# External_ADC.net
KiCad netlist of a schematic drawn in Altium Designer
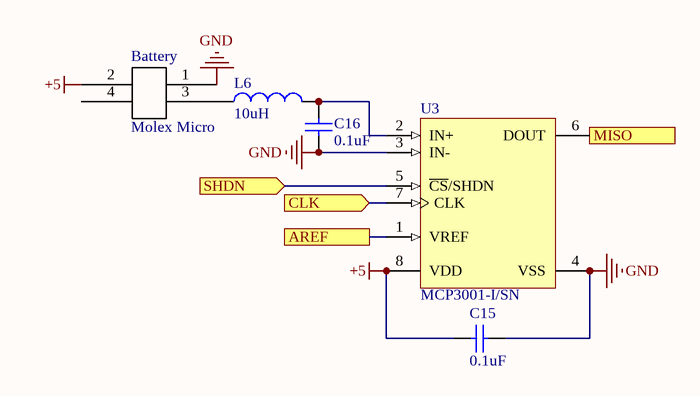
[diagram p0: External ADC.SchDoc]

(export (version "E")
  (design (tool "Eeschema 10.0.6"))
  (components
    (comp (ref "Battery")
      (value "Molex Micro")
      (footprint "0430450427")
      (description "Molex micro-fit 3.0, P/N 0430450427")
      (libsource (lib "Husky Robotics Standard Library 2019-2020") (part "Molex micro-fit 4-pin (dual row schematic)"))
    )
    (comp (ref "C15")
      (value "0.1uF")
      (footprint "CAPC2013X94X50LL20T25")
      (description "Chip Capacitor, 0.1 uF, +/- 5%, 50 V, -55 to 125 degC, 0805 (2012 Metric), RoHS, Tape and Reel")
      (fields (field (name "TOLERANCE") "5%") (field (name "MANUFACTURER") "AVX"))
      (libsource (lib "Altium Content Vault") (part "CAP-NP-2"))
    )
    (comp (ref "C16")
      (value "0.1uF")
      (footprint "CAPC2013X94X50LL20T25")
      (description "Chip Capacitor, 0.1 uF, +/- 5%, 50 V, -55 to 125 degC, 0805 (2012 Metric), RoHS, Tape and Reel")
      (fields (field (name "TOLERANCE") "5%") (field (name "MANUFACTURER") "AVX"))
      (libsource (lib "Altium Content Vault") (part "CAP-NP-2"))
    )
    (comp (ref "L6")
      (value "10uH")
      (footprint "TDK-IND0805-125_V")
      (description "Multilayer Inductor, 10 uH, ±20%, 300 mOhm, 50MHz, 0805(2012)")
      (fields (field (name "PARTNUMBER") "MLZ2012N100LT"))
      (libsource (lib "Altium Content Vault") (part "TDK-IND_INDUCTOR-2"))
    )
    (comp (ref "U3")
      (value "MCP3001-I/SN")
      (footprint "SOIC-SN8_M")
      (description "2.7V 10-Bit A/D Converter with SPI Serial Interface, 8-Pin SOIC 150mil, Industrial Temperature")
      (libsource (lib "Altium Content Vault") (part "CON-ADC-MCP3001-8"))
    )
  )
  (nets
    (net (code "1") (name "+5") (class "Default")
      (node (ref "Battery") (pin "2") (pintype "passive"))
      (node (ref "C15") (pin "2") (pinfunction "2_2") (pintype "passive"))
      (node (ref "U3") (pin "8") (pinfunction "VDD_8") (pintype "power_in"))
    )
    (net (code "2") (name "/AREF") (class "Default")
      (node (ref "U3") (pin "1") (pinfunction "VREF_1") (pintype "input"))
    )
    (net (code "3") (name "/CLK") (class "Default")
      (node (ref "U3") (pin "7") (pinfunction "CLK_7") (pintype "input"))
    )
    (net (code "4") (name "/MISO") (class "Default")
      (node (ref "U3") (pin "6") (pinfunction "DOUT_6") (pintype "tri_state"))
    )
    (net (code "5") (name "/SHDN") (class "Default")
      (node (ref "U3") (pin "5") (pinfunction "~{CS}/SHDN_5") (pintype "input"))
    )
    (net (code "6") (name "GND") (class "Default")
      (node (ref "Battery") (pin "1") (pintype "passive"))
      (node (ref "C15") (pin "1") (pinfunction "1_1") (pintype "passive"))
      (node (ref "C16") (pin "1") (pinfunction "1_1") (pintype "passive"))
      (node (ref "U3") (pin "3") (pinfunction "IN-_3") (pintype "input"))
      (node (ref "U3") (pin "4") (pinfunction "VSS_4") (pintype "power_in"))
    )
    (net (code "7") (name "Net-(Battery-Pad3)") (class "Default")
      (node (ref "Battery") (pin "3") (pintype "passive"))
      (node (ref "L6") (pin "1") (pinfunction "1_1") (pintype "passive"))
    )
    (net (code "8") (name "Net-(U3-IN+)") (class "Default")
      (node (ref "C16") (pin "2") (pinfunction "2_2") (pintype "passive"))
      (node (ref "L6") (pin "2") (pinfunction "2_2") (pintype "passive"))
      (node (ref "U3") (pin "2") (pinfunction "IN+_2") (pintype "input"))
    )
    (net (code "9") (name "unconnected-(Battery-Pad4)") (class "Default")
      (node (ref "Battery") (pin "4") (pintype "passive"))
    )
  )
)
